# CLKB_uplinks.net
KiCad netlist of a schematic drawn in Altium Designer
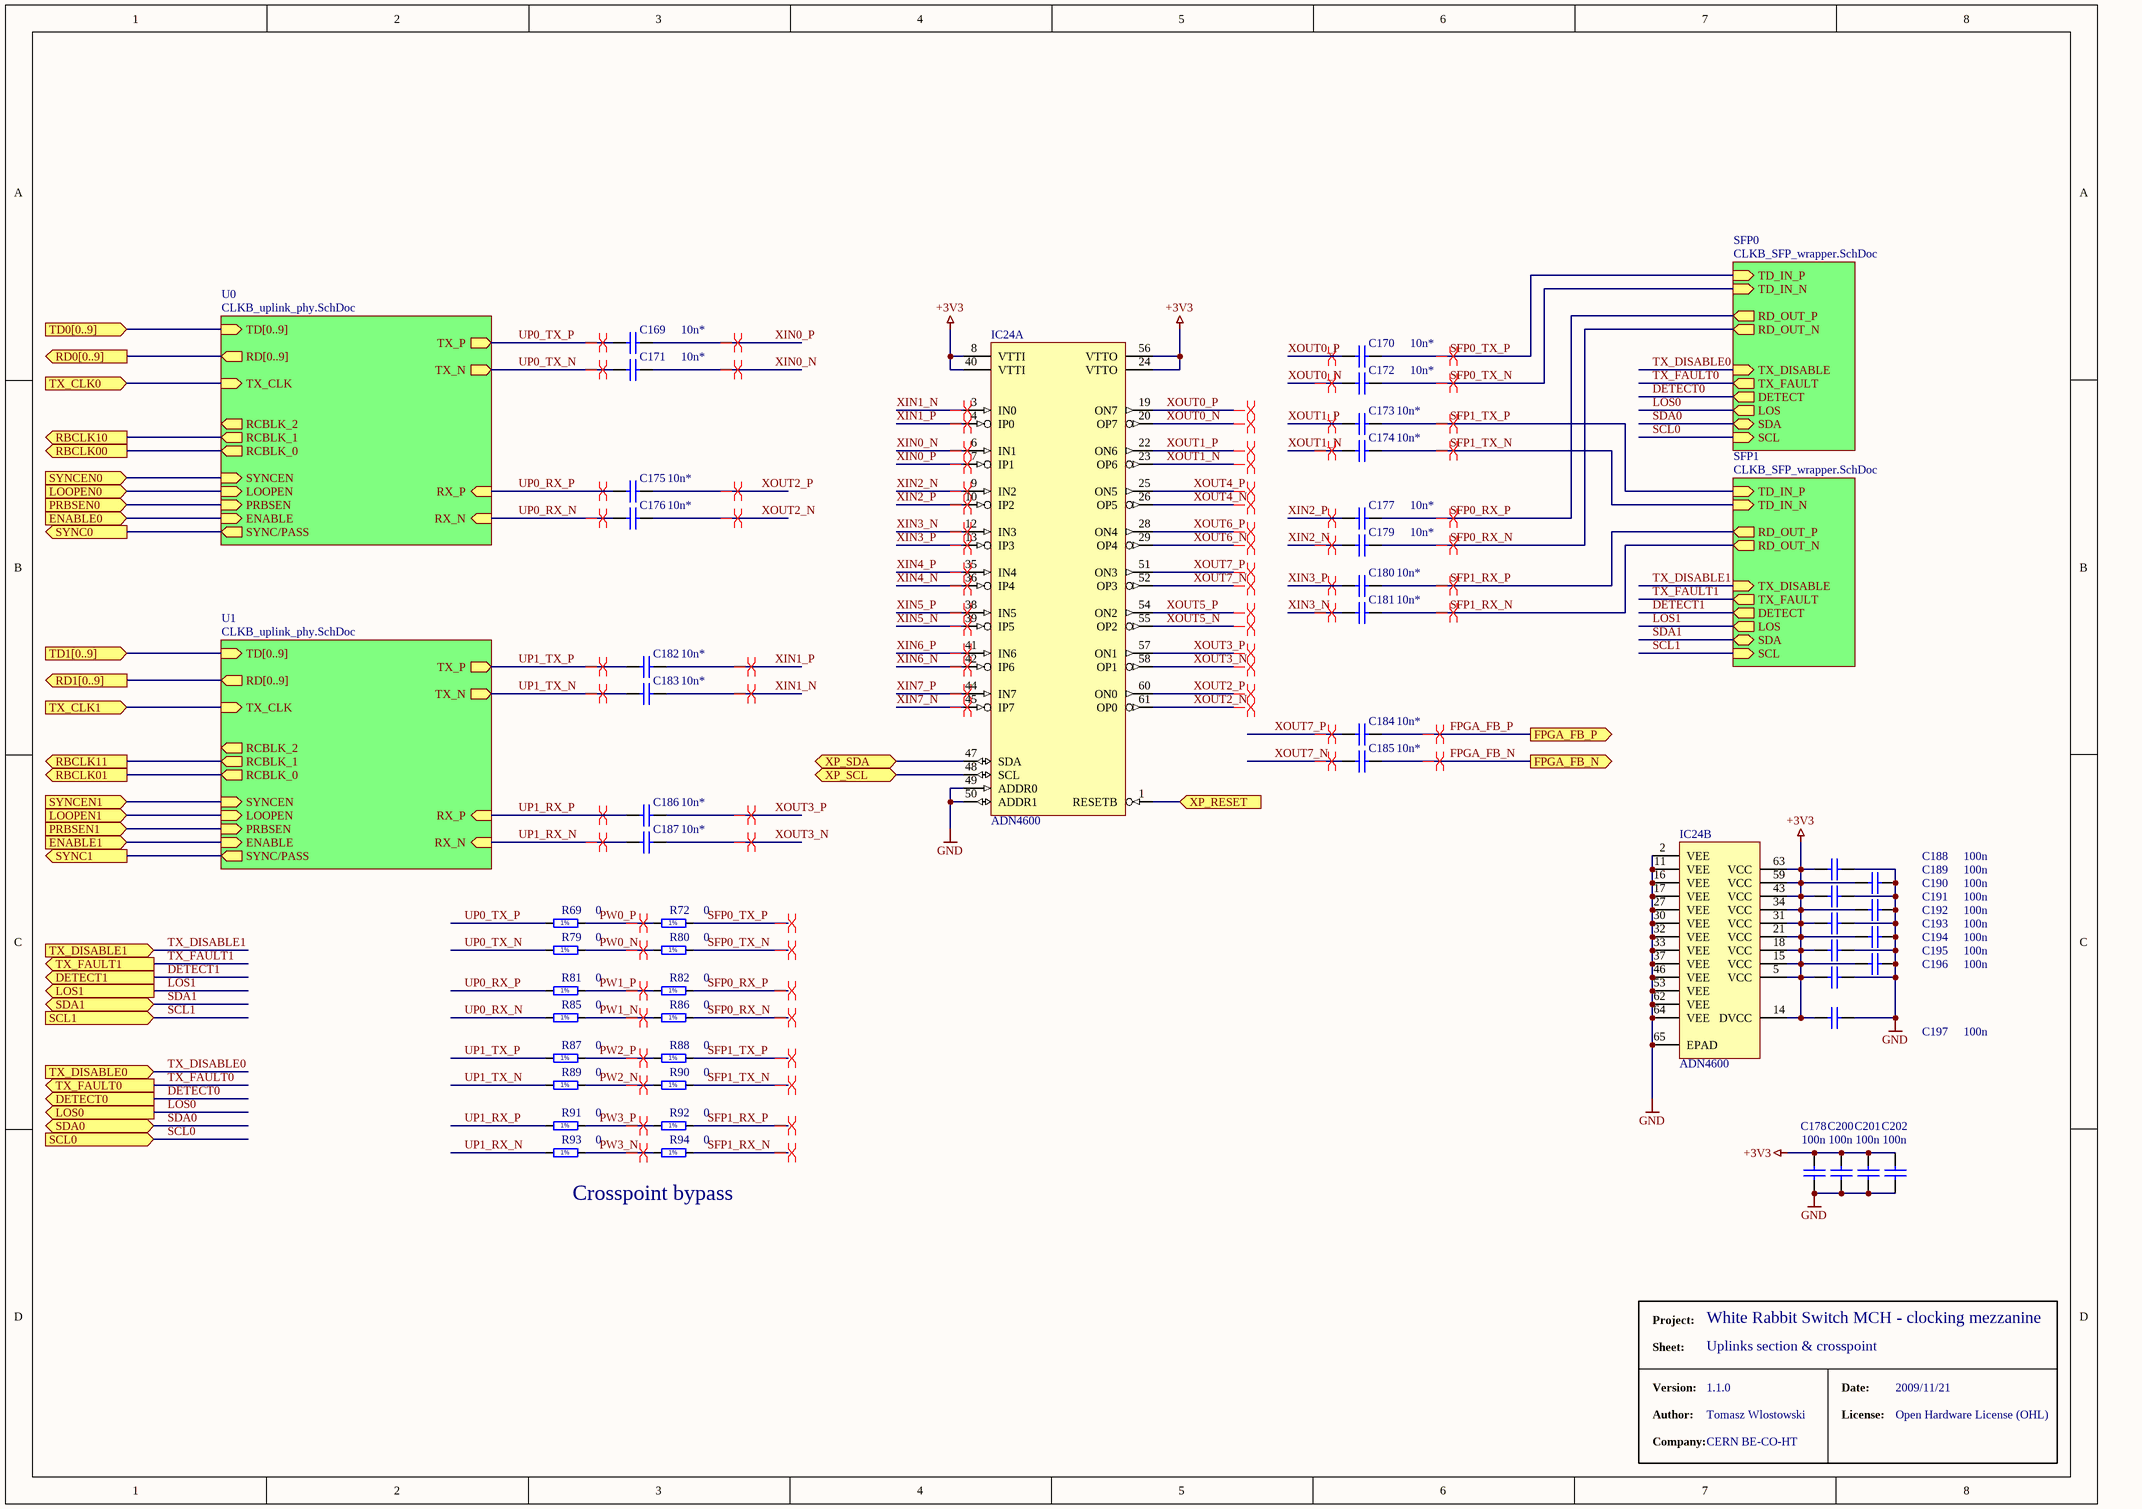
[diagram p0: CLKB_uplinks.SchDoc]

(export (version "E")
  (design (tool "Eeschema 10.0.6"))
  (components
    (comp (ref "C169")
      (value "10n*")
      (footprint "CAPC1005X55N")
      (description "Non-polarised capacitor")
      (fields
        (field (name "PART NUMBER") "CC0402_10NF_16V_10%_X7R")
        (field (name "VOLTAGE") "16V")
        (field (name "AUTHOR") "CERN DEM JLC")
      )
      (libsource (lib "Capacitors") (part "Capacitor - non polarized"))
    )
    (comp (ref "C170")
      (value "10n*")
      (footprint "CAPC1005X55N")
      (description "Non-polarised capacitor")
      (fields
        (field (name "PART NUMBER") "CC0402_10NF_16V_10%_X7R")
        (field (name "VOLTAGE") "16V")
        (field (name "AUTHOR") "CERN DEM JLC")
      )
      (libsource (lib "Capacitors") (part "Capacitor - non polarized"))
    )
    (comp (ref "C171")
      (value "10n*")
      (footprint "CAPC1005X55N")
      (description "Non-polarised capacitor")
      (fields
        (field (name "PART NUMBER") "CC0402_10NF_16V_10%_X7R")
        (field (name "VOLTAGE") "16V")
        (field (name "AUTHOR") "CERN DEM JLC")
      )
      (libsource (lib "Capacitors") (part "Capacitor - non polarized"))
    )
    (comp (ref "C172")
      (value "10n*")
      (footprint "CAPC1005X55N")
      (description "Non-polarised capacitor")
      (fields
        (field (name "PART NUMBER") "CC0402_10NF_16V_10%_X7R")
        (field (name "VOLTAGE") "16V")
        (field (name "AUTHOR") "CERN DEM JLC")
      )
      (libsource (lib "Capacitors") (part "Capacitor - non polarized"))
    )
    (comp (ref "C173")
      (value "10n*")
      (footprint "CAPC1005X55N")
      (description "Non-polarised capacitor")
      (fields
        (field (name "PART NUMBER") "CC0402_10NF_16V_10%_X7R")
        (field (name "VOLTAGE") "16V")
        (field (name "AUTHOR") "CERN DEM JLC")
      )
      (libsource (lib "Capacitors") (part "Capacitor - non polarized"))
    )
    (comp (ref "C174")
      (value "10n*")
      (footprint "CAPC1005X55N")
      (description "Non-polarised capacitor")
      (fields
        (field (name "PART NUMBER") "CC0402_10NF_16V_10%_X7R")
        (field (name "VOLTAGE") "16V")
        (field (name "AUTHOR") "CERN DEM JLC")
      )
      (libsource (lib "Capacitors") (part "Capacitor - non polarized"))
    )
    (comp (ref "C175")
      (value "10n*")
      (footprint "CAPC1005X55N")
      (description "Non-polarised capacitor")
      (fields
        (field (name "PART NUMBER") "CC0402_10NF_16V_10%_X7R")
        (field (name "VOLTAGE") "16V")
        (field (name "AUTHOR") "CERN DEM JLC")
      )
      (libsource (lib "Capacitors") (part "Capacitor - non polarized"))
    )
    (comp (ref "C176")
      (value "10n*")
      (footprint "CAPC1005X55N")
      (description "Non-polarised capacitor")
      (fields
        (field (name "PART NUMBER") "CC0402_10NF_16V_10%_X7R")
        (field (name "VOLTAGE") "16V")
        (field (name "AUTHOR") "CERN DEM JLC")
      )
      (libsource (lib "Capacitors") (part "Capacitor - non polarized"))
    )
    (comp (ref "C177")
      (value "10n*")
      (footprint "CAPC1005X55N")
      (description "Non-polarised capacitor")
      (fields
        (field (name "PART NUMBER") "CC0402_10NF_16V_10%_X7R")
        (field (name "VOLTAGE") "16V")
        (field (name "AUTHOR") "CERN DEM JLC")
      )
      (libsource (lib "Capacitors") (part "Capacitor - non polarized"))
    )
    (comp (ref "C178")
      (value "100n")
      (footprint "CAPC1005X55N")
      (description "Non-polarised capacitor")
      (fields
        (field (name "PART NUMBER") "CC0402_100NF_16V_10%_X7R")
        (field (name "VOLTAGE") "16V")
        (field (name "AUTHOR") "CERN DEM JLC")
      )
      (libsource (lib "Capacitors") (part "Capacitor - non polarized"))
    )
    (comp (ref "C179")
      (value "10n*")
      (footprint "CAPC1005X55N")
      (description "Non-polarised capacitor")
      (fields
        (field (name "PART NUMBER") "CC0402_10NF_16V_10%_X7R")
        (field (name "VOLTAGE") "16V")
        (field (name "AUTHOR") "CERN DEM JLC")
      )
      (libsource (lib "Capacitors") (part "Capacitor - non polarized"))
    )
    (comp (ref "C180")
      (value "10n*")
      (footprint "CAPC1005X55N")
      (description "Non-polarised capacitor")
      (fields
        (field (name "PART NUMBER") "CC0402_10NF_16V_10%_X7R")
        (field (name "VOLTAGE") "16V")
        (field (name "AUTHOR") "CERN DEM JLC")
      )
      (libsource (lib "Capacitors") (part "Capacitor - non polarized"))
    )
    (comp (ref "C181")
      (value "10n*")
      (footprint "CAPC1005X55N")
      (description "Non-polarised capacitor")
      (fields
        (field (name "PART NUMBER") "CC0402_10NF_16V_10%_X7R")
        (field (name "VOLTAGE") "16V")
        (field (name "AUTHOR") "CERN DEM JLC")
      )
      (libsource (lib "Capacitors") (part "Capacitor - non polarized"))
    )
    (comp (ref "C182")
      (value "10n*")
      (footprint "CAPC1005X55N")
      (description "Non-polarised capacitor")
      (fields
        (field (name "PART NUMBER") "CC0402_10NF_16V_10%_X7R")
        (field (name "VOLTAGE") "16V")
        (field (name "AUTHOR") "CERN DEM JLC")
      )
      (libsource (lib "Capacitors") (part "Capacitor - non polarized"))
    )
    (comp (ref "C183")
      (value "10n*")
      (footprint "CAPC1005X55N")
      (description "Non-polarised capacitor")
      (fields
        (field (name "PART NUMBER") "CC0402_10NF_16V_10%_X7R")
        (field (name "VOLTAGE") "16V")
        (field (name "AUTHOR") "CERN DEM JLC")
      )
      (libsource (lib "Capacitors") (part "Capacitor - non polarized"))
    )
    (comp (ref "C184")
      (value "10n*")
      (footprint "CAPC1005X55N")
      (description "Non-polarised capacitor")
      (fields
        (field (name "PART NUMBER") "CC0402_10NF_16V_10%_X7R")
        (field (name "VOLTAGE") "16V")
        (field (name "AUTHOR") "CERN DEM JLC")
      )
      (libsource (lib "Capacitors") (part "Capacitor - non polarized"))
    )
    (comp (ref "C185")
      (value "10n*")
      (footprint "CAPC1005X55N")
      (description "Non-polarised capacitor")
      (fields
        (field (name "PART NUMBER") "CC0402_10NF_16V_10%_X7R")
        (field (name "VOLTAGE") "16V")
        (field (name "AUTHOR") "CERN DEM JLC")
      )
      (libsource (lib "Capacitors") (part "Capacitor - non polarized"))
    )
    (comp (ref "C186")
      (value "10n*")
      (footprint "CAPC1005X55N")
      (description "Non-polarised capacitor")
      (fields
        (field (name "PART NUMBER") "CC0402_10NF_16V_10%_X7R")
        (field (name "VOLTAGE") "16V")
        (field (name "AUTHOR") "CERN DEM JLC")
      )
      (libsource (lib "Capacitors") (part "Capacitor - non polarized"))
    )
    (comp (ref "C187")
      (value "10n*")
      (footprint "CAPC1005X55N")
      (description "Non-polarised capacitor")
      (fields
        (field (name "PART NUMBER") "CC0402_10NF_16V_10%_X7R")
        (field (name "VOLTAGE") "16V")
        (field (name "AUTHOR") "CERN DEM JLC")
      )
      (libsource (lib "Capacitors") (part "Capacitor - non polarized"))
    )
    (comp (ref "C188")
      (value "100n")
      (footprint "CAPC1005X55N")
      (description "Non-polarised capacitor")
      (fields
        (field (name "PART NUMBER") "CC0402_100NF_16V_10%_X7R")
        (field (name "VOLTAGE") "16V")
        (field (name "AUTHOR") "CERN DEM JLC")
      )
      (libsource (lib "Capacitors") (part "Capacitor - non polarized"))
    )
    (comp (ref "C189")
      (value "100n")
      (footprint "CAPC1005X55N")
      (description "Non-polarised capacitor")
      (fields
        (field (name "PART NUMBER") "CC0402_100NF_16V_10%_X7R")
        (field (name "VOLTAGE") "16V")
        (field (name "AUTHOR") "CERN DEM JLC")
      )
      (libsource (lib "Capacitors") (part "Capacitor - non polarized"))
    )
    (comp (ref "C190")
      (value "100n")
      (footprint "CAPC1005X55N")
      (description "Non-polarised capacitor")
      (fields
        (field (name "PART NUMBER") "CC0402_100NF_16V_10%_X7R")
        (field (name "VOLTAGE") "16V")
        (field (name "AUTHOR") "CERN DEM JLC")
      )
      (libsource (lib "Capacitors") (part "Capacitor - non polarized"))
    )
    (comp (ref "C191")
      (value "100n")
      (footprint "CAPC1005X55N")
      (description "Non-polarised capacitor")
      (fields
        (field (name "PART NUMBER") "CC0402_100NF_16V_10%_X7R")
        (field (name "VOLTAGE") "16V")
        (field (name "AUTHOR") "CERN DEM JLC")
      )
      (libsource (lib "Capacitors") (part "Capacitor - non polarized"))
    )
    (comp (ref "C192")
      (value "100n")
      (footprint "CAPC1005X55N")
      (description "Non-polarised capacitor")
      (fields
        (field (name "PART NUMBER") "CC0402_100NF_16V_10%_X7R")
        (field (name "VOLTAGE") "16V")
        (field (name "AUTHOR") "CERN DEM JLC")
      )
      (libsource (lib "Capacitors") (part "Capacitor - non polarized"))
    )
    (comp (ref "C193")
      (value "100n")
      (footprint "CAPC1005X55N")
      (description "Non-polarised capacitor")
      (fields
        (field (name "PART NUMBER") "CC0402_100NF_16V_10%_X7R")
        (field (name "VOLTAGE") "16V")
        (field (name "AUTHOR") "CERN DEM JLC")
      )
      (libsource (lib "Capacitors") (part "Capacitor - non polarized"))
    )
    (comp (ref "C194")
      (value "100n")
      (footprint "CAPC1005X55N")
      (description "Non-polarised capacitor")
      (fields
        (field (name "PART NUMBER") "CC0402_100NF_16V_10%_X7R")
        (field (name "VOLTAGE") "16V")
        (field (name "AUTHOR") "CERN DEM JLC")
      )
      (libsource (lib "Capacitors") (part "Capacitor - non polarized"))
    )
    (comp (ref "C195")
      (value "100n")
      (footprint "CAPC1005X55N")
      (description "Non-polarised capacitor")
      (fields
        (field (name "PART NUMBER") "CC0402_100NF_16V_10%_X7R")
        (field (name "VOLTAGE") "16V")
        (field (name "AUTHOR") "CERN DEM JLC")
      )
      (libsource (lib "Capacitors") (part "Capacitor - non polarized"))
    )
    (comp (ref "C196")
      (value "100n")
      (footprint "CAPC1005X55N")
      (description "Non-polarised capacitor")
      (fields
        (field (name "PART NUMBER") "CC0402_100NF_16V_10%_X7R")
        (field (name "VOLTAGE") "16V")
        (field (name "AUTHOR") "CERN DEM JLC")
      )
      (libsource (lib "Capacitors") (part "Capacitor - non polarized"))
    )
    (comp (ref "C197")
      (value "100n")
      (footprint "CAPC1005X55N")
      (description "Non-polarised capacitor")
      (fields
        (field (name "PART NUMBER") "CC0402_100NF_16V_10%_X7R")
        (field (name "VOLTAGE") "16V")
        (field (name "AUTHOR") "CERN DEM JLC")
      )
      (libsource (lib "Capacitors") (part "Capacitor - non polarized"))
    )
    (comp (ref "C200")
      (value "100n")
      (footprint "CAPC1005X55N")
      (description "Non-polarised capacitor")
      (fields
        (field (name "PART NUMBER") "CC0402_100NF_16V_10%_X7R")
        (field (name "VOLTAGE") "16V")
        (field (name "AUTHOR") "CERN DEM JLC")
      )
      (libsource (lib "Capacitors") (part "Capacitor - non polarized"))
    )
    (comp (ref "C201")
      (value "100n")
      (footprint "CAPC1005X55N")
      (description "Non-polarised capacitor")
      (fields
        (field (name "PART NUMBER") "CC0402_100NF_16V_10%_X7R")
        (field (name "VOLTAGE") "16V")
        (field (name "AUTHOR") "CERN DEM JLC")
      )
      (libsource (lib "Capacitors") (part "Capacitor - non polarized"))
    )
    (comp (ref "C202")
      (value "100n")
      (footprint "CAPC1005X55N")
      (description "Non-polarised capacitor")
      (fields
        (field (name "PART NUMBER") "CC0402_100NF_16V_10%_X7R")
        (field (name "VOLTAGE") "16V")
        (field (name "AUTHOR") "CERN DEM JLC")
      )
      (libsource (lib "Capacitors") (part "Capacitor - non polarized"))
    )
    (comp (ref "IC24")
      (value "ADN4600")
      (footprint "LFCSP64_ADN4600")
      (description "Gigabit 8x8 crosspoint switch")
      (libsource (lib "wr_switch") (part "ADN4600"))
    )
    (comp (ref "R69")
      (value "0")
      (footprint "RESC1005X40N")
      (description "Resistor - 1%")
      (fields
        (field (name "PART NUMBER") "R0402_0R_JUMPER")
        (field (name "MANUFACTURER") "GENERIC")
        (field (name "AUTHOR") "CERN DEM JLC")
      )
      (libsource (lib "Resistors") (part "Resistor - 1%"))
    )
    (comp (ref "R72")
      (value "0")
      (footprint "RESC1005X40N")
      (description "Resistor - 1%")
      (fields
        (field (name "PART NUMBER") "R0402_0R_JUMPER")
        (field (name "MANUFACTURER") "GENERIC")
        (field (name "AUTHOR") "CERN DEM JLC")
      )
      (libsource (lib "Resistors") (part "Resistor - 1%"))
    )
    (comp (ref "R79")
      (value "0")
      (footprint "RESC1005X40N")
      (description "Resistor - 1%")
      (fields
        (field (name "PART NUMBER") "R0402_0R_JUMPER")
        (field (name "MANUFACTURER") "GENERIC")
        (field (name "AUTHOR") "CERN DEM JLC")
      )
      (libsource (lib "Resistors") (part "Resistor - 1%"))
    )
    (comp (ref "R80")
      (value "0")
      (footprint "RESC1005X40N")
      (description "Resistor - 1%")
      (fields
        (field (name "PART NUMBER") "R0402_0R_JUMPER")
        (field (name "MANUFACTURER") "GENERIC")
        (field (name "AUTHOR") "CERN DEM JLC")
      )
      (libsource (lib "Resistors") (part "Resistor - 1%"))
    )
    (comp (ref "R81")
      (value "0")
      (footprint "RESC1005X40N")
      (description "Resistor - 1%")
      (fields
        (field (name "PART NUMBER") "R0402_0R_JUMPER")
        (field (name "MANUFACTURER") "GENERIC")
        (field (name "AUTHOR") "CERN DEM JLC")
      )
      (libsource (lib "Resistors") (part "Resistor - 1%"))
    )
    (comp (ref "R82")
      (value "0")
      (footprint "RESC1005X40N")
      (description "Resistor - 1%")
      (fields
        (field (name "PART NUMBER") "R0402_0R_JUMPER")
        (field (name "MANUFACTURER") "GENERIC")
        (field (name "AUTHOR") "CERN DEM JLC")
      )
      (libsource (lib "Resistors") (part "Resistor - 1%"))
    )
    (comp (ref "R85")
      (value "0")
      (footprint "RESC1005X40N")
      (description "Resistor - 1%")
      (fields
        (field (name "PART NUMBER") "R0402_0R_JUMPER")
        (field (name "MANUFACTURER") "GENERIC")
        (field (name "AUTHOR") "CERN DEM JLC")
      )
      (libsource (lib "Resistors") (part "Resistor - 1%"))
    )
    (comp (ref "R86")
      (value "0")
      (footprint "RESC1005X40N")
      (description "Resistor - 1%")
      (fields
        (field (name "PART NUMBER") "R0402_0R_JUMPER")
        (field (name "MANUFACTURER") "GENERIC")
        (field (name "AUTHOR") "CERN DEM JLC")
      )
      (libsource (lib "Resistors") (part "Resistor - 1%"))
    )
    (comp (ref "R87")
      (value "0")
      (footprint "RESC1005X40N")
      (description "Resistor - 1%")
      (fields
        (field (name "PART NUMBER") "R0402_0R_JUMPER")
        (field (name "MANUFACTURER") "GENERIC")
        (field (name "AUTHOR") "CERN DEM JLC")
      )
      (libsource (lib "Resistors") (part "Resistor - 1%"))
    )
    (comp (ref "R88")
      (value "0")
      (footprint "RESC1005X40N")
      (description "Resistor - 1%")
      (fields
        (field (name "PART NUMBER") "R0402_0R_JUMPER")
        (field (name "MANUFACTURER") "GENERIC")
        (field (name "AUTHOR") "CERN DEM JLC")
      )
      (libsource (lib "Resistors") (part "Resistor - 1%"))
    )
    (comp (ref "R89")
      (value "0")
      (footprint "RESC1005X40N")
      (description "Resistor - 1%")
      (fields
        (field (name "PART NUMBER") "R0402_0R_JUMPER")
        (field (name "MANUFACTURER") "GENERIC")
        (field (name "AUTHOR") "CERN DEM JLC")
      )
      (libsource (lib "Resistors") (part "Resistor - 1%"))
    )
    (comp (ref "R90")
      (value "0")
      (footprint "RESC1005X40N")
      (description "Resistor - 1%")
      (fields
        (field (name "PART NUMBER") "R0402_0R_JUMPER")
        (field (name "MANUFACTURER") "GENERIC")
        (field (name "AUTHOR") "CERN DEM JLC")
      )
      (libsource (lib "Resistors") (part "Resistor - 1%"))
    )
    (comp (ref "R91")
      (value "0")
      (footprint "RESC1005X40N")
      (description "Resistor - 1%")
      (fields
        (field (name "PART NUMBER") "R0402_0R_JUMPER")
        (field (name "MANUFACTURER") "GENERIC")
        (field (name "AUTHOR") "CERN DEM JLC")
      )
      (libsource (lib "Resistors") (part "Resistor - 1%"))
    )
    (comp (ref "R92")
      (value "0")
      (footprint "RESC1005X40N")
      (description "Resistor - 1%")
      (fields
        (field (name "PART NUMBER") "R0402_0R_JUMPER")
        (field (name "MANUFACTURER") "GENERIC")
        (field (name "AUTHOR") "CERN DEM JLC")
      )
      (libsource (lib "Resistors") (part "Resistor - 1%"))
    )
    (comp (ref "R93")
      (value "0")
      (footprint "RESC1005X40N")
      (description "Resistor - 1%")
      (fields
        (field (name "PART NUMBER") "R0402_0R_JUMPER")
        (field (name "MANUFACTURER") "GENERIC")
        (field (name "AUTHOR") "CERN DEM JLC")
      )
      (libsource (lib "Resistors") (part "Resistor - 1%"))
    )
    (comp (ref "R94")
      (value "0")
      (footprint "RESC1005X40N")
      (description "Resistor - 1%")
      (fields
        (field (name "PART NUMBER") "R0402_0R_JUMPER")
        (field (name "MANUFACTURER") "GENERIC")
        (field (name "AUTHOR") "CERN DEM JLC")
      )
      (libsource (lib "Resistors") (part "Resistor - 1%"))
    )
  )
  (nets
    (net (code "41") (name "+3V3") (class "Default")
      (node (ref "C178") (pin "2") (pinfunction "2_2") (pintype "passive"))
      (node (ref "C188") (pin "1") (pinfunction "1_1") (pintype "passive"))
      (node (ref "C189") (pin "1") (pinfunction "1_1") (pintype "passive"))
      (node (ref "C190") (pin "1") (pinfunction "1_1") (pintype "passive"))
      (node (ref "C191") (pin "1") (pinfunction "1_1") (pintype "passive"))
      (node (ref "C192") (pin "1") (pinfunction "1_1") (pintype "passive"))
      (node (ref "C193") (pin "1") (pinfunction "1_1") (pintype "passive"))
      (node (ref "C194") (pin "1") (pinfunction "1_1") (pintype "passive"))
      (node (ref "C195") (pin "1") (pinfunction "1_1") (pintype "passive"))
      (node (ref "C196") (pin "1") (pinfunction "1_1") (pintype "passive"))
      (node (ref "C197") (pin "1") (pinfunction "1_1") (pintype "passive"))
      (node (ref "C200") (pin "2") (pinfunction "2_2") (pintype "passive"))
      (node (ref "C201") (pin "2") (pinfunction "2_2") (pintype "passive"))
      (node (ref "C202") (pin "2") (pinfunction "2_2") (pintype "passive"))
      (node (ref "IC24") (pin "14") (pinfunction "DVCC_14") (pintype "power_in"))
      (node (ref "IC24") (pin "15") (pinfunction "VCC_15") (pintype "power_in"))
      (node (ref "IC24") (pin "18") (pinfunction "VCC_18") (pintype "power_in"))
      (node (ref "IC24") (pin "21") (pinfunction "VCC_21") (pintype "power_in"))
      (node (ref "IC24") (pin "24") (pinfunction "VTTO_24") (pintype "power_in"))
      (node (ref "IC24") (pin "31") (pinfunction "VCC_31") (pintype "power_in"))
      (node (ref "IC24") (pin "34") (pinfunction "VCC_34") (pintype "power_in"))
      (node (ref "IC24") (pin "40") (pinfunction "VTTI_40") (pintype "power_in"))
      (node (ref "IC24") (pin "43") (pinfunction "VCC_43") (pintype "power_in"))
      (node (ref "IC24") (pin "5") (pinfunction "VCC_5") (pintype "power_in"))
      (node (ref "IC24") (pin "56") (pinfunction "VTTO_56") (pintype "power_in"))
      (node (ref "IC24") (pin "59") (pinfunction "VCC_59") (pintype "power_in"))
      (node (ref "IC24") (pin "63") (pinfunction "VCC_63") (pintype "power_in"))
      (node (ref "IC24") (pin "8") (pinfunction "VTTI_8") (pintype "power_in"))
    )
    (net (code "46") (name "/FPGA_FB_N") (class "Default")
      (node (ref "C185") (pin "2") (pinfunction "2_2") (pintype "passive"))
    )
    (net (code "47") (name "/FPGA_FB_P") (class "Default")
      (node (ref "C184") (pin "2") (pinfunction "2_2") (pintype "passive"))
    )
    (net (code "54") (name "/PW0_N") (class "Default")
      (node (ref "R79") (pin "2") (pinfunction "2_2") (pintype "passive"))
      (node (ref "R80") (pin "1") (pinfunction "1_1") (pintype "passive"))
    )
    (net (code "55") (name "/PW0_P") (class "Default")
      (node (ref "R69") (pin "2") (pinfunction "2_2") (pintype "passive"))
      (node (ref "R72") (pin "1") (pinfunction "1_1") (pintype "passive"))
    )
    (net (code "56") (name "/PW1_N") (class "Default")
      (node (ref "R85") (pin "2") (pinfunction "2_2") (pintype "passive"))
      (node (ref "R86") (pin "1") (pinfunction "1_1") (pintype "passive"))
    )
    (net (code "57") (name "/PW1_P") (class "Default")
      (node (ref "R81") (pin "2") (pinfunction "2_2") (pintype "passive"))
      (node (ref "R82") (pin "1") (pinfunction "1_1") (pintype "passive"))
    )
    (net (code "58") (name "/PW2_N") (class "Default")
      (node (ref "R89") (pin "2") (pinfunction "2_2") (pintype "passive"))
      (node (ref "R90") (pin "1") (pinfunction "1_1") (pintype "passive"))
    )
    (net (code "59") (name "/PW2_P") (class "Default")
      (node (ref "R87") (pin "2") (pinfunction "2_2") (pintype "passive"))
      (node (ref "R88") (pin "1") (pinfunction "1_1") (pintype "passive"))
    )
    (net (code "60") (name "/PW3_N") (class "Default")
      (node (ref "R93") (pin "2") (pinfunction "2_2") (pintype "passive"))
      (node (ref "R94") (pin "1") (pinfunction "1_1") (pintype "passive"))
    )
    (net (code "61") (name "/PW3_P") (class "Default")
      (node (ref "R91") (pin "2") (pinfunction "2_2") (pintype "passive"))
      (node (ref "R92") (pin "1") (pinfunction "1_1") (pintype "passive"))
    )
    (net (code "74") (name "/SFP0_RX_N") (class "Default")
      (node (ref "C179") (pin "2") (pinfunction "2_2") (pintype "passive"))
      (node (ref "R86") (pin "2") (pinfunction "2_2") (pintype "passive"))
    )
    (net (code "75") (name "/SFP0_RX_P") (class "Default")
      (node (ref "C177") (pin "2") (pinfunction "2_2") (pintype "passive"))
      (node (ref "R82") (pin "2") (pinfunction "2_2") (pintype "passive"))
    )
    (net (code "76") (name "/SFP0_TX_N") (class "Default")
      (node (ref "C172") (pin "2") (pinfunction "2_2") (pintype "passive"))
      (node (ref "R80") (pin "2") (pinfunction "2_2") (pintype "passive"))
    )
    (net (code "77") (name "/SFP0_TX_P") (class "Default")
      (node (ref "C170") (pin "2") (pinfunction "2_2") (pintype "passive"))
      (node (ref "R72") (pin "2") (pinfunction "2_2") (pintype "passive"))
    )
    (net (code "78") (name "/SFP1_RX_N") (class "Default")
      (node (ref "C181") (pin "2") (pinfunction "2_2") (pintype "passive"))
      (node (ref "R94") (pin "2") (pinfunction "2_2") (pintype "passive"))
    )
    (net (code "79") (name "/SFP1_RX_P") (class "Default")
      (node (ref "C180") (pin "2") (pinfunction "2_2") (pintype "passive"))
      (node (ref "R92") (pin "2") (pinfunction "2_2") (pintype "passive"))
    )
    (net (code "80") (name "/SFP1_TX_N") (class "Default")
      (node (ref "C174") (pin "2") (pinfunction "2_2") (pintype "passive"))
      (node (ref "R90") (pin "2") (pinfunction "2_2") (pintype "passive"))
    )
    (net (code "81") (name "/SFP1_TX_P") (class "Default")
      (node (ref "C173") (pin "2") (pinfunction "2_2") (pintype "passive"))
      (node (ref "R88") (pin "2") (pinfunction "2_2") (pintype "passive"))
    )
    (net (code "94") (name "/UP0_RX_N") (class "Default")
      (node (ref "C176") (pin "1") (pinfunction "1_1") (pintype "passive"))
      (node (ref "R85") (pin "1") (pinfunction "1_1") (pintype "passive"))
    )
    (net (code "95") (name "/UP0_RX_P") (class "Default")
      (node (ref "C175") (pin "1") (pinfunction "1_1") (pintype "passive"))
      (node (ref "R81") (pin "1") (pinfunction "1_1") (pintype "passive"))
    )
    (net (code "96") (name "/UP0_TX_N") (class "Default")
      (node (ref "C171") (pin "1") (pinfunction "1_1") (pintype "passive"))
      (node (ref "R79") (pin "1") (pinfunction "1_1") (pintype "passive"))
    )
    (net (code "97") (name "/UP0_TX_P") (class "Default")
      (node (ref "C169") (pin "1") (pinfunction "1_1") (pintype "passive"))
      (node (ref "R69") (pin "1") (pinfunction "1_1") (pintype "passive"))
    )
    (net (code "98") (name "/UP1_RX_N") (class "Default")
      (node (ref "C187") (pin "1") (pinfunction "1_1") (pintype "passive"))
      (node (ref "R93") (pin "1") (pinfunction "1_1") (pintype "passive"))
    )
    (net (code "99") (name "/UP1_RX_P") (class "Default")
      (node (ref "C186") (pin "1") (pinfunction "1_1") (pintype "passive"))
      (node (ref "R91") (pin "1") (pinfunction "1_1") (pintype "passive"))
    )
    (net (code "100") (name "/UP1_TX_N") (class "Default")
      (node (ref "C183") (pin "1") (pinfunction "1_1") (pintype "passive"))
      (node (ref "R89") (pin "1") (pinfunction "1_1") (pintype "passive"))
    )
    (net (code "101") (name "/UP1_TX_P") (class "Default")
      (node (ref "C182") (pin "1") (pinfunction "1_1") (pintype "passive"))
      (node (ref "R87") (pin "1") (pinfunction "1_1") (pintype "passive"))
    )
    (net (code "102") (name "/XIN0_N") (class "Default")
      (node (ref "C171") (pin "2") (pinfunction "2_2") (pintype "passive"))
      (node (ref "IC24") (pin "6") (pinfunction "IN1_6") (pintype "input"))
    )
    (net (code "103") (name "/XIN0_P") (class "Default")
      (node (ref "C169") (pin "2") (pinfunction "2_2") (pintype "passive"))
      (node (ref "IC24") (pin "7") (pinfunction "IP1_7") (pintype "input"))
    )
    (net (code "104") (name "/XIN1_N") (class "Default")
      (node (ref "C183") (pin "2") (pinfunction "2_2") (pintype "passive"))
      (node (ref "IC24") (pin "3") (pinfunction "IN0_3") (pintype "input"))
    )
    (net (code "105") (name "/XIN1_P") (class "Default")
      (node (ref "C182") (pin "2") (pinfunction "2_2") (pintype "passive"))
      (node (ref "IC24") (pin "4") (pinfunction "IP0_4") (pintype "input"))
    )
    (net (code "106") (name "/XIN2_N") (class "Default")
      (node (ref "C179") (pin "1") (pinfunction "1_1") (pintype "passive"))
      (node (ref "IC24") (pin "9") (pinfunction "IN2_9") (pintype "input"))
    )
    (net (code "107") (name "/XIN2_P") (class "Default")
      (node (ref "C177") (pin "1") (pinfunction "1_1") (pintype "passive"))
      (node (ref "IC24") (pin "10") (pinfunction "IP2_10") (pintype "input"))
    )
    (net (code "108") (name "/XIN3_N") (class "Default")
      (node (ref "C181") (pin "1") (pinfunction "1_1") (pintype "passive"))
      (node (ref "IC24") (pin "12") (pinfunction "IN3_12") (pintype "input"))
    )
    (net (code "109") (name "/XIN3_P") (class "Default")
      (node (ref "C180") (pin "1") (pinfunction "1_1") (pintype "passive"))
      (node (ref "IC24") (pin "13") (pinfunction "IP3_13") (pintype "input"))
    )
    (net (code "110") (name "/XIN4_N") (class "Default")
      (node (ref "IC24") (pin "36") (pinfunction "IP4_36") (pintype "input"))
    )
    (net (code "111") (name "/XIN4_P") (class "Default")
      (node (ref "IC24") (pin "35") (pinfunction "IN4_35") (pintype "input"))
    )
    (net (code "112") (name "/XIN5_N") (class "Default")
      (node (ref "IC24") (pin "39") (pinfunction "IP5_39") (pintype "input"))
    )
    (net (code "113") (name "/XIN5_P") (class "Default")
      (node (ref "IC24") (pin "38") (pinfunction "IN5_38") (pintype "input"))
    )
    (net (code "114") (name "/XIN6_N") (class "Default")
      (node (ref "IC24") (pin "42") (pinfunction "IP6_42") (pintype "input"))
    )
    (net (code "115") (name "/XIN6_P") (class "Default")
      (node (ref "IC24") (pin "41") (pinfunction "IN6_41") (pintype "input"))
    )
    (net (code "116") (name "/XIN7_N") (class "Default")
      (node (ref "IC24") (pin "45") (pinfunction "IP7_45") (pintype "input"))
    )
    (net (code "117") (name "/XIN7_P") (class "Default")
      (node (ref "IC24") (pin "44") (pinfunction "IN7_44") (pintype "input"))
    )
    (net (code "118") (name "/XOUT0_N") (class "Default")
      (node (ref "C172") (pin "1") (pinfunction "1_1") (pintype "passive"))
      (node (ref "IC24") (pin "20") (pinfunction "OP7_20") (pintype "output"))
    )
    (net (code "119") (name "/XOUT0_P") (class "Default")
      (node (ref "C170") (pin "1") (pinfunction "1_1") (pintype "passive"))
      (node (ref "IC24") (pin "19") (pinfunction "ON7_19") (pintype "output"))
    )
    (net (code "120") (name "/XOUT1_N") (class "Default")
      (node (ref "C174") (pin "1") (pinfunction "1_1") (pintype "passive"))
      (node (ref "IC24") (pin "23") (pinfunction "OP6_23") (pintype "output"))
    )
    (net (code "121") (name "/XOUT1_P") (class "Default")
      (node (ref "C173") (pin "1") (pinfunction "1_1") (pintype "passive"))
      (node (ref "IC24") (pin "22") (pinfunction "ON6_22") (pintype "output"))
    )
    (net (code "122") (name "/XOUT2_N") (class "Default")
      (node (ref "C176") (pin "2") (pinfunction "2_2") (pintype "passive"))
      (node (ref "IC24") (pin "61") (pinfunction "OP0_61") (pintype "output"))
    )
    (net (code "123") (name "/XOUT2_P") (class "Default")
      (node (ref "C175") (pin "2") (pinfunction "2_2") (pintype "passive"))
      (node (ref "IC24") (pin "60") (pinfunction "ON0_60") (pintype "output"))
    )
    (net (code "124") (name "/XOUT3_N") (class "Default")
      (node (ref "C187") (pin "2") (pinfunction "2_2") (pintype "passive"))
      (node (ref "IC24") (pin "58") (pinfunction "OP1_58") (pintype "output"))
    )
    (net (code "125") (name "/XOUT3_P") (class "Default")
      (node (ref "C186") (pin "2") (pinfunction "2_2") (pintype "passive"))
      (node (ref "IC24") (pin "57") (pinfunction "ON1_57") (pintype "output"))
    )
    (net (code "126") (name "/XOUT4_N") (class "Default")
      (node (ref "IC24") (pin "26") (pinfunction "OP5_26") (pintype "output"))
    )
    (net (code "127") (name "/XOUT4_P") (class "Default")
      (node (ref "IC24") (pin "25") (pinfunction "ON5_25") (pintype "output"))
    )
    (net (code "128") (name "/XOUT5_N") (class "Default")
      (node (ref "IC24") (pin "55") (pinfunction "OP2_55") (pintype "output"))
    )
    (net (code "129") (name "/XOUT5_P") (class "Default")
      (node (ref "IC24") (pin "54") (pinfunction "ON2_54") (pintype "output"))
    )
    (net (code "130") (name "/XOUT6_N") (class "Default")
      (node (ref "IC24") (pin "29") (pinfunction "OP4_29") (pintype "output"))
    )
    (net (code "131") (name "/XOUT6_P") (class "Default")
      (node (ref "IC24") (pin "28") (pinfunction "ON4_28") (pintype "output"))
    )
    (net (code "132") (name "/XOUT7_N") (class "Default")
      (node (ref "C185") (pin "1") (pinfunction "1_1") (pintype "passive"))
      (node (ref "IC24") (pin "52") (pinfunction "OP3_52") (pintype "output"))
    )
    (net (code "133") (name "/XOUT7_P") (class "Default")
      (node (ref "C184") (pin "1") (pinfunction "1_1") (pintype "passive"))
      (node (ref "IC24") (pin "51") (pinfunction "ON3_51") (pintype "output"))
    )
    (net (code "134") (name "/XP_RESET") (class "Default")
      (node (ref "IC24") (pin "1") (pinfunction "RESETB_1") (pintype "input"))
    )
    (net (code "135") (name "/XP_SCL") (class "Default")
      (node (ref "IC24") (pin "48") (pinfunction "SCL_48") (pintype "bidirectional"))
    )
    (net (code "136") (name "/XP_SDA") (class "Default")
      (node (ref "IC24") (pin "47") (pinfunction "SDA_47") (pintype "bidirectional"))
    )
    (net (code "137") (name "GND") (class "Default")
      (node (ref "C178") (pin "1") (pinfunction "1_1") (pintype "passive"))
      (node (ref "C188") (pin "2") (pinfunction "2_2") (pintype "passive"))
      (node (ref "C189") (pin "2") (pinfunction "2_2") (pintype "passive"))
      (node (ref "C190") (pin "2") (pinfunction "2_2") (pintype "passive"))
      (node (ref "C191") (pin "2") (pinfunction "2_2") (pintype "passive"))
      (node (ref "C192") (pin "2") (pinfunction "2_2") (pintype "passive"))
      (node (ref "C193") (pin "2") (pinfunction "2_2") (pintype "passive"))
      (node (ref "C194") (pin "2") (pinfunction "2_2") (pintype "passive"))
      (node (ref "C195") (pin "2") (pinfunction "2_2") (pintype "passive"))
      (node (ref "C196") (pin "2") (pinfunction "2_2") (pintype "passive"))
      (node (ref "C197") (pin "2") (pinfunction "2_2") (pintype "passive"))
      (node (ref "C200") (pin "1") (pinfunction "1_1") (pintype "passive"))
      (node (ref "C201") (pin "1") (pinfunction "1_1") (pintype "passive"))
      (node (ref "C202") (pin "1") (pinfunction "1_1") (pintype "passive"))
      (node (ref "IC24") (pin "11") (pinfunction "VEE_11") (pintype "power_in"))
      (node (ref "IC24") (pin "16") (pinfunction "VEE_16") (pintype "power_in"))
      (node (ref "IC24") (pin "17") (pinfunction "VEE_17") (pintype "power_in"))
      (node (ref "IC24") (pin "2") (pinfunction "VEE_2") (pintype "power_in"))
      (node (ref "IC24") (pin "27") (pinfunction "VEE_27") (pintype "power_in"))
      (node (ref "IC24") (pin "30") (pinfunction "VEE_30") (pintype "power_in"))
      (node (ref "IC24") (pin "32") (pinfunction "VEE_32") (pintype "power_in"))
      (node (ref "IC24") (pin "33") (pinfunction "VEE_33") (pintype "power_in"))
      (node (ref "IC24") (pin "37") (pinfunction "VEE_37") (pintype "power_in"))
      (node (ref "IC24") (pin "46") (pinfunction "VEE_46") (pintype "power_in"))
      (node (ref "IC24") (pin "49") (pinfunction "ADDR0_49") (pintype "input"))
      (node (ref "IC24") (pin "50") (pinfunction "ADDR1_50") (pintype "bidirectional"))
      (node (ref "IC24") (pin "53") (pinfunction "VEE_53") (pintype "power_in"))
      (node (ref "IC24") (pin "62") (pinfunction "VEE_62") (pintype "power_in"))
      (node (ref "IC24") (pin "64") (pinfunction "VEE_64") (pintype "power_in"))
      (node (ref "IC24") (pin "65") (pinfunction "EPAD_65") (pintype "power_in"))
    )
  )
)
